# HoloCubicPowerV02_220109.net
KiCad netlist of a schematic drawn in Altium Designer
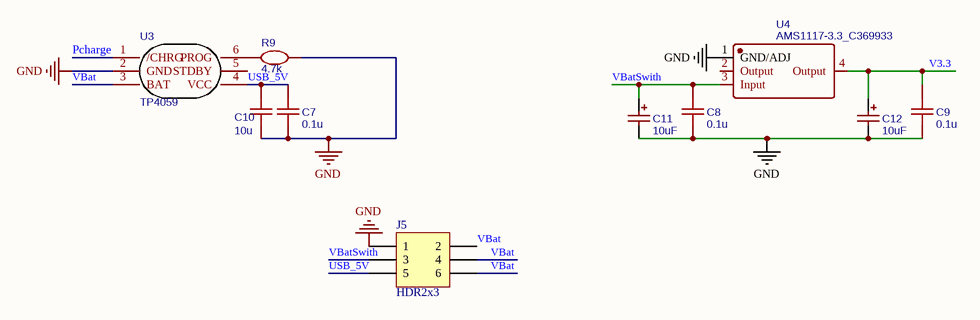
[diagram p0: HoloCubicPowerV02_220109.SchDoc]

(export (version "E")
  (design (tool "Eeschema 10.0.6"))
  (components
    (comp (ref "C7")
      (value "0.1u")
      (footprint "C0603")
      (fields (field (name "CONTRIBUTOR") "LCEDA_Lib"))
      (libsource (lib "altium-import") (part "root_1_0.1u_"))
    )
    (comp (ref "C8")
      (value "0.1u")
      (footprint "C0603")
      (fields (field (name "CONTRIBUTOR") "LCEDA_Lib"))
      (libsource (lib "altium-import") (part "root_1_0.1u_"))
    )
    (comp (ref "C9")
      (value "0.1u")
      (footprint "C0603")
      (fields (field (name "CONTRIBUTOR") "LCEDA_Lib"))
      (libsource (lib "altium-import") (part "root_1_0.1u_"))
    )
    (comp (ref "C10")
      (value "10u")
      (footprint "C0603")
      (fields (field (name "CONTRIBUTOR") "LCEDA_Lib"))
      (libsource (lib "altium-import") (part "root_1_0.1u_"))
    )
    (comp (ref "C11")
      (value "10uF")
      (footprint "CAP-SMD_L3.2-W1.6-R-RD")
      (fields
        (field (name "BOM_MANUFACTURER PART") "CA45-A-16V-10uF-K")
        (field (name "BOM_SUPPLIER PART") "C128254")
        (field (name "CONTRIBUTOR") "LCSC")
      )
      (libsource (lib "altium-import") (part "root_1_10uF_"))
    )
    (comp (ref "C12")
      (value "10uF")
      (footprint "CAP-SMD_L3.2-W1.6-R-RD")
      (fields
        (field (name "BOM_MANUFACTURER PART") "CA45-A-16V-10uF-K")
        (field (name "BOM_SUPPLIER PART") "C128254")
        (field (name "CONTRIBUTOR") "LCSC")
      )
      (libsource (lib "altium-import") (part "root_1_10uF_"))
    )
    (comp (ref "J5")
      (value "HDR2x3")
      (footprint "PIN-2x3-2.54-1.0")
      (description "Connector")
      (libsource (lib "General") (part "HDR2x3"))
    )
    (comp (ref "R9")
      (value "4.7k")
      (footprint "R0603")
      (fields (field (name "CONTRIBUTOR") "LCEDA_Lib"))
      (libsource (lib "altium-import") (part "root_2_10k_"))
    )
    (comp (ref "U3")
      (value "TP4059")
      (footprint "SOT-23-6")
      (fields (field (name "BOM_SUPPLIER PART") "C80364"))
      (libsource (lib "ZtYADLib") (part "TP4059"))
    )
    (comp (ref "U4")
      (value "AMS1117-3.3_C369933")
      (footprint "SOT-223-4_L6.5-W3.5-P2.30-LS7.0-BR")
      (fields
        (field (name "BOM_SUPPLIER PART") "C369933")
        (field (name "BOM_MANUFACTURER PART") "AMS1117-3.3")
        (field (name "CONTRIBUTOR") "LCSC")
      )
      (libsource (lib "altium-import") (part "root_0_AMS1117-3.3_C369933_"))
    )
  )
  (nets
    (net (code "1") (name "/Pcharge") (class "Default")
      (node (ref "U3") (pin "1") (pinfunction "/CHRG_1") (pintype "passive"))
    )
    (net (code "2") (name "/USB_5V") (class "Default")
      (node (ref "C10") (pin "2") (pinfunction "2_2") (pintype "passive"))
      (node (ref "C7") (pin "2") (pinfunction "2_2") (pintype "passive"))
      (node (ref "J5") (pin "5") (pinfunction "5_5") (pintype "passive"))
      (node (ref "U3") (pin "4") (pinfunction "VCC_4") (pintype "passive"))
    )
    (net (code "3") (name "/V3.3") (class "Default")
      (node (ref "C12") (pin "1") (pinfunction "1_1") (pintype "passive"))
      (node (ref "C9") (pin "2") (pinfunction "2_2") (pintype "passive"))
      (node (ref "U4") (pin "4") (pinfunction "Output_4") (pintype "passive"))
    )
    (net (code "4") (name "/VBat") (class "Default")
      (node (ref "J5") (pin "2") (pinfunction "2_2") (pintype "passive"))
      (node (ref "J5") (pin "4") (pinfunction "4_4") (pintype "passive"))
      (node (ref "J5") (pin "6") (pinfunction "6_6") (pintype "passive"))
      (node (ref "U3") (pin "3") (pinfunction "BAT_3") (pintype "passive"))
    )
    (net (code "5") (name "/VBatSwith") (class "Default")
      (node (ref "C11") (pin "1") (pinfunction "1_1") (pintype "passive"))
      (node (ref "C8") (pin "2") (pinfunction "2_2") (pintype "passive"))
      (node (ref "J5") (pin "3") (pinfunction "3_3") (pintype "passive"))
      (node (ref "U4") (pin "3") (pinfunction "Input_3") (pintype "passive"))
    )
    (net (code "6") (name "GND") (class "Default")
      (node (ref "C10") (pin "1") (pinfunction "1_1") (pintype "passive"))
      (node (ref "C11") (pin "2") (pinfunction "2_2") (pintype "passive"))
      (node (ref "C12") (pin "2") (pinfunction "2_2") (pintype "passive"))
      (node (ref "C7") (pin "1") (pinfunction "1_1") (pintype "passive"))
      (node (ref "C8") (pin "1") (pinfunction "1_1") (pintype "passive"))
      (node (ref "C9") (pin "1") (pinfunction "1_1") (pintype "passive"))
      (node (ref "J5") (pin "1") (pinfunction "1_1") (pintype "passive"))
      (node (ref "R9") (pin "1") (pinfunction "1_1") (pintype "passive"))
      (node (ref "U3") (pin "2") (pinfunction "GND_2") (pintype "passive"))
      (node (ref "U4") (pin "1") (pinfunction "GND/ADJ_1") (pintype "passive"))
    )
    (net (code "7") (name "Net-(U3-PROG)") (class "Default")
      (node (ref "R9") (pin "2") (pinfunction "2_2") (pintype "passive"))
      (node (ref "U3") (pin "6") (pinfunction "PROG_6") (pintype "passive"))
    )
    (net (code "8") (name "unconnected-(U3-STDBY-Pad5)") (class "Default")
      (node (ref "U3") (pin "5") (pinfunction "STDBY_5") (pintype "passive"))
    )
    (net (code "9") (name "unconnected-(U4-Output-Pad2)") (class "Default")
      (node (ref "U4") (pin "2") (pinfunction "Output_2") (pintype "passive"))
    )
  )
)
